# Power_lines.net
KiCad netlist of a schematic drawn in Altium Designer
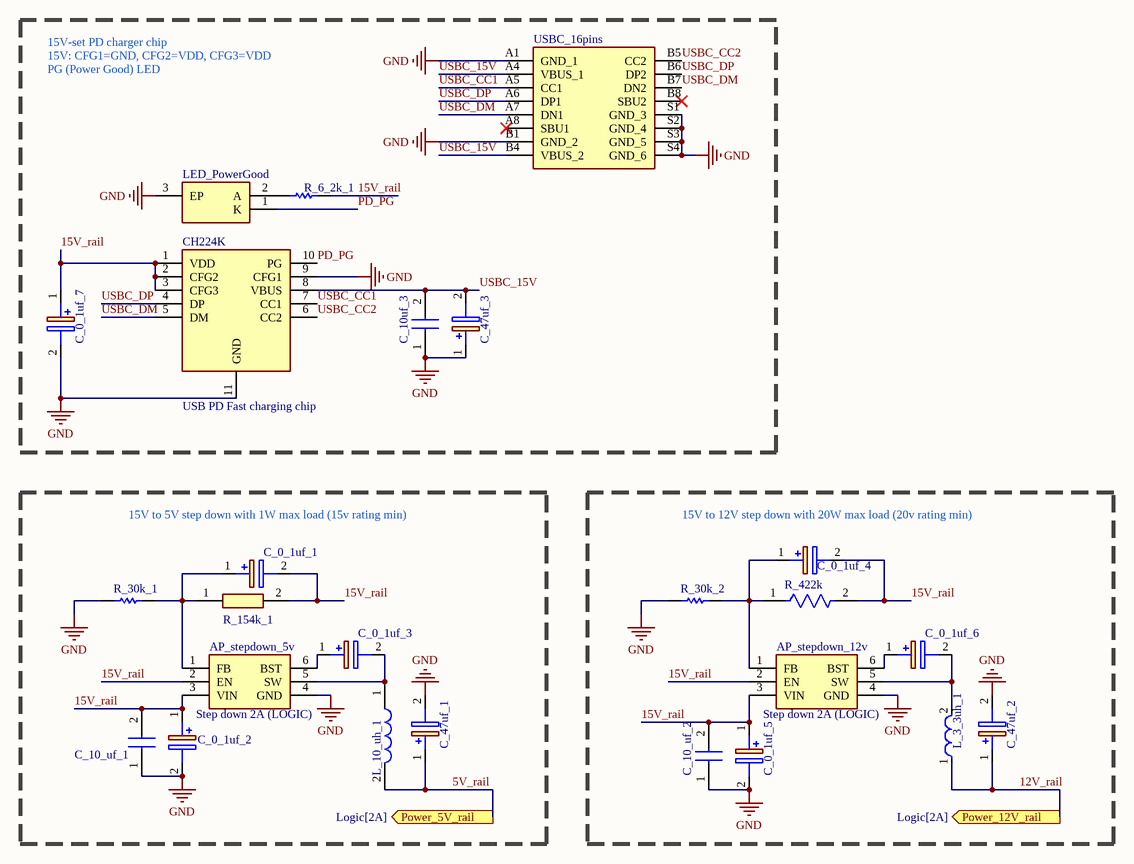
[diagram p0: Power_lines.SchDoc]

(export (version "E")
  (design (tool "Eeschema 10.0.6"))
  (components
    (comp (ref "AP_stepdown_5v")
      (value "Step down 2A (LOGIC)")
      (footprint "SamacSys:SOT95P280X100-6N")
      (description "Integrated Circuit")
      (fields
        (field (name "MANUFACTURER_PART_NUMBER") "AP63201WU-7")
        (field (name "MOUSER PART NUMBER") "621-AP63201WU-7")
      )
      (libsource (lib "*") (part "AP63201WU-7"))
    )
    (comp (ref "AP_stepdown_12v")
      (value "Step down 2A (LOGIC)")
      (footprint "SamacSys:SOT95P280X100-6N")
      (description "Integrated Circuit")
      (fields
        (field (name "MANUFACTURER_PART_NUMBER") "AP63201WU-7")
        (field (name "MOUSER PART NUMBER") "621-AP63201WU-7")
      )
      (libsource (lib "*") (part "AP63201WU-7"))
    )
    (comp (ref "CH224K")
      (value "USB PD Fast charging chip")
      (footprint "SamacSys:SOP100P600X180-11N")
      (description "Integrated Circuit")
      (fields (field (name "MANUFACTURER_PART_NUMBER") "CH224K"))
      (libsource (lib "*") (part "CH224K"))
    )
    (comp (ref "C_0_1uf_1")
      (value "TAJS104K020RNJ")
      (footprint "SamacSys:CAPPM3216X120N")
      (description "Capacitor Polarised")
      (fields (field (name "MOUSER PART NUMBER") "581-TAJS104K020RNJ"))
      (libsource (lib "") (part "TAJS104K020RNJ_1"))
    )
    (comp (ref "C_0_1uf_2")
      (value "TAJS104K020RNJ")
      (footprint "SamacSys:CAPPM3216X120N")
      (description "Capacitor Polarised")
      (fields (field (name "MOUSER PART NUMBER") "581-TAJS104K020RNJ"))
      (libsource (lib "*") (part "TAJS104K020RNJ"))
    )
    (comp (ref "C_0_1uf_3")
      (value "TAJS104K020RNJ")
      (footprint "SamacSys:CAPPM3216X120N")
      (description "Capacitor Polarised")
      (fields (field (name "MOUSER PART NUMBER") "581-TAJS104K020RNJ"))
      (libsource (lib "") (part "TAJS104K020RNJ_1"))
    )
    (comp (ref "C_0_1uf_4")
      (value "TAJS104K020RNJ")
      (footprint "SamacSys:CAPPM3216X120N")
      (description "Capacitor Polarised")
      (fields (field (name "MOUSER PART NUMBER") "581-TAJS104K020RNJ"))
      (libsource (lib "") (part "TAJS104K020RNJ_1"))
    )
    (comp (ref "C_0_1uf_5")
      (value "TAJS104K020RNJ")
      (footprint "SamacSys:CAPPM3216X120N")
      (description "Capacitor Polarised")
      (fields (field (name "MOUSER PART NUMBER") "581-TAJS104K020RNJ"))
      (libsource (lib "*") (part "TAJS104K020RNJ"))
    )
    (comp (ref "C_0_1uf_6")
      (value "TAJS104K020RNJ")
      (footprint "SamacSys:CAPPM3216X120N")
      (description "Capacitor Polarised")
      (fields (field (name "MOUSER PART NUMBER") "581-TAJS104K020RNJ"))
      (libsource (lib "") (part "TAJS104K020RNJ_1"))
    )
    (comp (ref "C_0_1uf_7")
      (value "TAJS104K020RNJ")
      (footprint "SamacSys:CAPPM3216X120N")
      (description "Capacitor Polarised")
      (fields (field (name "MOUSER PART NUMBER") "581-TAJS104K020RNJ"))
      (libsource (lib "*") (part "TAJS104K020RNJ"))
    )
    (comp (ref "C_10uf_3")
      (value "CL31B106KAHNFNE")
      (footprint "SamacSys:CAPC3216X180N")
      (description "Capacitor")
      (fields (field (name "MOUSER PART NUMBER") "187-CL31B106KAHNFNE"))
      (libsource (lib "*") (part "CL31B106KAHNFNE"))
    )
    (comp (ref "C_10_uf_1")
      (value "CL31B106KAHNFNE")
      (footprint "SamacSys:CAPC3216X180N")
      (description "Capacitor")
      (fields (field (name "MOUSER PART NUMBER") "187-CL31B106KAHNFNE"))
      (libsource (lib "*") (part "CL31B106KAHNFNE"))
    )
    (comp (ref "C_10_uf_2")
      (value "CL31B106KAHNFNE")
      (footprint "SamacSys:CAPC3216X180N")
      (description "Capacitor")
      (fields (field (name "MOUSER PART NUMBER") "187-CL31B106KAHNFNE"))
      (libsource (lib "*") (part "CL31B106KAHNFNE"))
    )
    (comp (ref "C_47uf_1")
      (value "TAJC476K020SNJ")
      (footprint "SamacSys:CAPPM6032X280N")
      (description "Capacitor Polarised")
      (fields (field (name "MOUSER PART NUMBER") "581-TAJC476K020SNJ"))
      (libsource (lib "*") (part "TAJC476K020SNJ"))
    )
    (comp (ref "C_47uf_2")
      (value "TAJC476K020SNJ")
      (footprint "SamacSys:CAPPM6032X280N")
      (description "Capacitor Polarised")
      (fields (field (name "MOUSER PART NUMBER") "581-TAJC476K020SNJ"))
      (libsource (lib "*") (part "TAJC476K020SNJ"))
    )
    (comp (ref "C_47uf_3")
      (value "TAJC476K020SNJ")
      (footprint "SamacSys:CAPPM6032X280N")
      (description "Capacitor Polarised")
      (fields (field (name "MOUSER PART NUMBER") "581-TAJC476K020SNJ"))
      (libsource (lib "*") (part "TAJC476K020SNJ"))
    )
    (comp (ref "LED_PowerGood")
      (value "IN-S126ASA")
      (footprint "SamacSys:INS126ASA")
      (description "LED")
      (fields (field (name "MOUSER PART NUMBER") "743-IN-S126ASA"))
      (libsource (lib "*") (part "IN-S126ASA"))
    )
    (comp (ref "L_3_3uh_1")
      (value "LQH5BPN3R3N38K")
      (footprint "FP-LQH5BPN_38-MFG")
      (description "Wire Wound Ferrite Inductor for Power Lines 3.3μH ±30% 0.0252Ω 4000mA 2020")
      (libsource (lib "Altium Content Vault") (part "725321dda6339637d4d059423bc1c3c"))
    )
    (comp (ref "L_10_uh_1")
      (value "SRR1260-100M")
      (footprint "SamacSys:SRR1260100M")
      (description "Inductor")
      (fields (field (name "MOUSER PART NUMBER") "652-SRR1260-100M"))
      (libsource (lib "*") (part "SRR1260-100M"))
    )
    (comp (ref "R_6_2k_1")
      (value "6K2 5% 2512(6432)")
      (footprint "RESC2512(6432)_L")
      (description "6K2 1W 5% 2512 (6432 Metric)  SMD")
      (fields (field (name "TOLERANCE") "5 %") (field (name "POWER") "1 W"))
      (libsource (lib "Altium Content Vault") (part "RES"))
    )
    (comp (ref "R_30k_1")
      (value "30K 1% 2512(6432)")
      (footprint "RESC2512(6432)_M")
      (description "30K 1W 1% 2512 (6432 Metric)  SMD")
      (fields (field (name "POWER") "1 W") (field (name "TOLERANCE") "1 %"))
      (libsource (lib "Altium Content Vault") (part "RES"))
    )
    (comp (ref "R_30k_2")
      (value "30K 1% 2512(6432)")
      (footprint "RESC2512(6432)_M")
      (description "30K 1W 1% 2512 (6432 Metric)  SMD")
      (fields (field (name "POWER") "1 W") (field (name "TOLERANCE") "1 %"))
      (libsource (lib "Altium Content Vault") (part "RES"))
    )
    (comp (ref "R_154k_1")
      (value "ERJ-8ENF1543V")
      (footprint "SamacSys:ERJ8ENF1000V")
      (description "Resistor")
      (fields (field (name "MOUSER PART NUMBER") "667-ERJ-8ENF1543V"))
      (libsource (lib "*") (part "ERJ-8ENF1543V"))
    )
    (comp (ref "R_422k")
      (value "CRCW2512422KFKEG")
      (footprint "FP-CRCW2512-e3-IPC_A")
      (description "RES Thick Film, 422kΩ, 1%, 1W, 100ppm/°C, 2512")
      (fields (field (name "TOLERANCE") "1%"))
      (libsource (lib "Altium Content Vault") (part "1029c3af85768c4190bb7ad29bc67b5"))
    )
    (comp (ref "USBC_16pins")
      (value "USB4940-00-A")
      (footprint "SamacSys:USB494000A")
      (description "Connector")
      (libsource (lib "*") (part "USB4940-00-A"))
    )
  )
  (nets
    (net (code "1") (name "/5V_rail") (class "Default")
      (node (ref "C_47uf_1") (pin "1") (pinfunction "+_1") (pintype "passive"))
      (node (ref "L_10_uh_1") (pin "2") (pinfunction "2_2") (pintype "passive"))
    )
    (net (code "2") (name "/12V_rail") (class "Default")
      (node (ref "C_47uf_2") (pin "1") (pinfunction "+_1") (pintype "passive"))
      (node (ref "L_3_3uh_1") (pin "1") (pinfunction "1_1") (pintype "passive"))
    )
    (net (code "3") (name "/15V_rail") (class "Default")
      (node (ref "AP_stepdown_12v") (pin "2") (pinfunction "EN_2") (pintype "passive"))
      (node (ref "AP_stepdown_12v") (pin "3") (pinfunction "VIN_3") (pintype "passive"))
      (node (ref "AP_stepdown_5v") (pin "2") (pinfunction "EN_2") (pintype "passive"))
      (node (ref "AP_stepdown_5v") (pin "3") (pinfunction "VIN_3") (pintype "passive"))
      (node (ref "CH224K") (pin "1") (pinfunction "VDD_1") (pintype "passive"))
      (node (ref "CH224K") (pin "2") (pinfunction "CFG2_2") (pintype "passive"))
      (node (ref "CH224K") (pin "3") (pinfunction "CFG3_3") (pintype "passive"))
      (node (ref "C_0_1uf_1") (pin "2") (pinfunction "-_2") (pintype "passive"))
      (node (ref "C_0_1uf_2") (pin "1") (pinfunction "+_1") (pintype "passive"))
      (node (ref "C_0_1uf_4") (pin "2") (pinfunction "-_2") (pintype "passive"))
      (node (ref "C_0_1uf_5") (pin "1") (pinfunction "+_1") (pintype "passive"))
      (node (ref "C_0_1uf_7") (pin "1") (pinfunction "+_1") (pintype "passive"))
      (node (ref "C_10_uf_1") (pin "2") (pinfunction "2_2") (pintype "passive"))
      (node (ref "C_10_uf_2") (pin "2") (pinfunction "2_2") (pintype "passive"))
      (node (ref "R_154k_1") (pin "2") (pinfunction "2_2") (pintype "passive"))
      (node (ref "R_422k") (pin "2") (pinfunction "2_2") (pintype "passive"))
      (node (ref "R_6_2k_1") (pin "2") (pinfunction "2_2") (pintype "passive"))
    )
    (net (code "4") (name "/PD_PG") (class "Default")
      (node (ref "CH224K") (pin "10") (pinfunction "PG_10") (pintype "passive"))
      (node (ref "LED_PowerGood") (pin "1") (pinfunction "K_1") (pintype "passive"))
    )
    (net (code "5") (name "/USBC_15V") (class "Default")
      (node (ref "CH224K") (pin "8") (pinfunction "VBUS_8") (pintype "passive"))
      (node (ref "C_10uf_3") (pin "2") (pinfunction "2_2") (pintype "passive"))
      (node (ref "C_47uf_3") (pin "2") (pinfunction "-_2") (pintype "passive"))
      (node (ref "USBC_16pins") (pin "A4") (pinfunction "VBUS_1_A4") (pintype "passive"))
      (node (ref "USBC_16pins") (pin "B4") (pinfunction "VBUS_2_B4") (pintype "passive"))
    )
    (net (code "6") (name "/USBC_CC1") (class "Default")
      (node (ref "CH224K") (pin "7") (pinfunction "CC1_7") (pintype "passive"))
      (node (ref "USBC_16pins") (pin "A5") (pinfunction "CC1_A5") (pintype "passive"))
    )
    (net (code "7") (name "/USBC_CC2") (class "Default")
      (node (ref "CH224K") (pin "6") (pinfunction "CC2_6") (pintype "passive"))
      (node (ref "USBC_16pins") (pin "B5") (pinfunction "CC2_B5") (pintype "passive"))
    )
    (net (code "8") (name "/USBC_DM") (class "Default")
      (node (ref "CH224K") (pin "5") (pinfunction "DM_5") (pintype "passive"))
      (node (ref "USBC_16pins") (pin "A7") (pinfunction "DN1_A7") (pintype "passive"))
      (node (ref "USBC_16pins") (pin "B7") (pinfunction "DN2_B7") (pintype "passive"))
    )
    (net (code "9") (name "/USBC_DP") (class "Default")
      (node (ref "CH224K") (pin "4") (pinfunction "DP_4") (pintype "passive"))
      (node (ref "USBC_16pins") (pin "A6") (pinfunction "DP1_A6") (pintype "passive"))
      (node (ref "USBC_16pins") (pin "B6") (pinfunction "DP2_B6") (pintype "passive"))
    )
    (net (code "10") (name "GND") (class "Default")
      (node (ref "AP_stepdown_12v") (pin "4") (pinfunction "GND_4") (pintype "passive"))
      (node (ref "AP_stepdown_5v") (pin "4") (pinfunction "GND_4") (pintype "passive"))
      (node (ref "CH224K") (pin "11") (pinfunction "GND_11") (pintype "passive"))
      (node (ref "CH224K") (pin "9") (pinfunction "CFG1_9") (pintype "passive"))
      (node (ref "C_0_1uf_2") (pin "2") (pinfunction "-_2") (pintype "passive"))
      (node (ref "C_0_1uf_5") (pin "2") (pinfunction "-_2") (pintype "passive"))
      (node (ref "C_0_1uf_7") (pin "2") (pinfunction "-_2") (pintype "passive"))
      (node (ref "C_10_uf_1") (pin "1") (pinfunction "1_1") (pintype "passive"))
      (node (ref "C_10_uf_2") (pin "1") (pinfunction "1_1") (pintype "passive"))
      (node (ref "C_10uf_3") (pin "1") (pinfunction "1_1") (pintype "passive"))
      (node (ref "C_47uf_1") (pin "2") (pinfunction "-_2") (pintype "passive"))
      (node (ref "C_47uf_2") (pin "2") (pinfunction "-_2") (pintype "passive"))
      (node (ref "C_47uf_3") (pin "1") (pinfunction "+_1") (pintype "passive"))
      (node (ref "LED_PowerGood") (pin "3") (pinfunction "EP_3") (pintype "passive"))
      (node (ref "R_30k_1") (pin "1") (pinfunction "1_1") (pintype "passive"))
      (node (ref "R_30k_2") (pin "1") (pinfunction "1_1") (pintype "passive"))
      (node (ref "USBC_16pins") (pin "A1") (pinfunction "GND_1_A1") (pintype "passive"))
      (node (ref "USBC_16pins") (pin "B1") (pinfunction "GND_2_B1") (pintype "passive"))
      (node (ref "USBC_16pins") (pin "S1") (pinfunction "GND_3_S1") (pintype "passive"))
      (node (ref "USBC_16pins") (pin "S2") (pinfunction "GND_4_S2") (pintype "passive"))
      (node (ref "USBC_16pins") (pin "S3") (pinfunction "GND_5_S3") (pintype "passive"))
      (node (ref "USBC_16pins") (pin "S4") (pinfunction "GND_6_S4") (pintype "passive"))
    )
    (net (code "11") (name "Net-(AP_stepdown_5v-BST)") (class "Default")
      (node (ref "AP_stepdown_5v") (pin "6") (pinfunction "BST_6") (pintype "passive"))
      (node (ref "C_0_1uf_3") (pin "1") (pinfunction "+_1") (pintype "passive"))
    )
    (net (code "12") (name "Net-(AP_stepdown_5v-FB)") (class "Default")
      (node (ref "AP_stepdown_5v") (pin "1") (pinfunction "FB_1") (pintype "passive"))
      (node (ref "C_0_1uf_1") (pin "1") (pinfunction "+_1") (pintype "passive"))
      (node (ref "R_154k_1") (pin "1") (pinfunction "1_1") (pintype "passive"))
      (node (ref "R_30k_1") (pin "2") (pinfunction "2_2") (pintype "passive"))
    )
    (net (code "13") (name "Net-(AP_stepdown_5v-SW)") (class "Default")
      (node (ref "AP_stepdown_5v") (pin "5") (pinfunction "SW_5") (pintype "passive"))
      (node (ref "C_0_1uf_3") (pin "2") (pinfunction "-_2") (pintype "passive"))
      (node (ref "L_10_uh_1") (pin "1") (pinfunction "1_1") (pintype "passive"))
    )
    (net (code "14") (name "Net-(AP_stepdown_12v-BST)") (class "Default")
      (node (ref "AP_stepdown_12v") (pin "6") (pinfunction "BST_6") (pintype "passive"))
      (node (ref "C_0_1uf_6") (pin "1") (pinfunction "+_1") (pintype "passive"))
    )
    (net (code "15") (name "Net-(AP_stepdown_12v-FB)") (class "Default")
      (node (ref "AP_stepdown_12v") (pin "1") (pinfunction "FB_1") (pintype "passive"))
      (node (ref "C_0_1uf_4") (pin "1") (pinfunction "+_1") (pintype "passive"))
      (node (ref "R_30k_2") (pin "2") (pinfunction "2_2") (pintype "passive"))
      (node (ref "R_422k") (pin "1") (pinfunction "1_1") (pintype "passive"))
    )
    (net (code "16") (name "Net-(AP_stepdown_12v-SW)") (class "Default")
      (node (ref "AP_stepdown_12v") (pin "5") (pinfunction "SW_5") (pintype "passive"))
      (node (ref "C_0_1uf_6") (pin "2") (pinfunction "-_2") (pintype "passive"))
      (node (ref "L_3_3uh_1") (pin "2") (pinfunction "2_2") (pintype "passive"))
    )
    (net (code "17") (name "Net-(LED_PowerGood-A)") (class "Default")
      (node (ref "LED_PowerGood") (pin "2") (pinfunction "A_2") (pintype "passive"))
      (node (ref "R_6_2k_1") (pin "1") (pinfunction "1_1") (pintype "passive"))
    )
    (net (code "18") (name "unconnected-(USBC_16pins-SBU1-PadA8)") (class "Default")
      (node (ref "USBC_16pins") (pin "A8") (pinfunction "SBU1_A8") (pintype "passive+no_connect"))
    )
    (net (code "19") (name "unconnected-(USBC_16pins-SBU2-PadB8)") (class "Default")
      (node (ref "USBC_16pins") (pin "B8") (pinfunction "SBU2_B8") (pintype "passive+no_connect"))
    )
  )
)
